# Schematic.net
KiCad netlist of a schematic drawn in Altium Designer
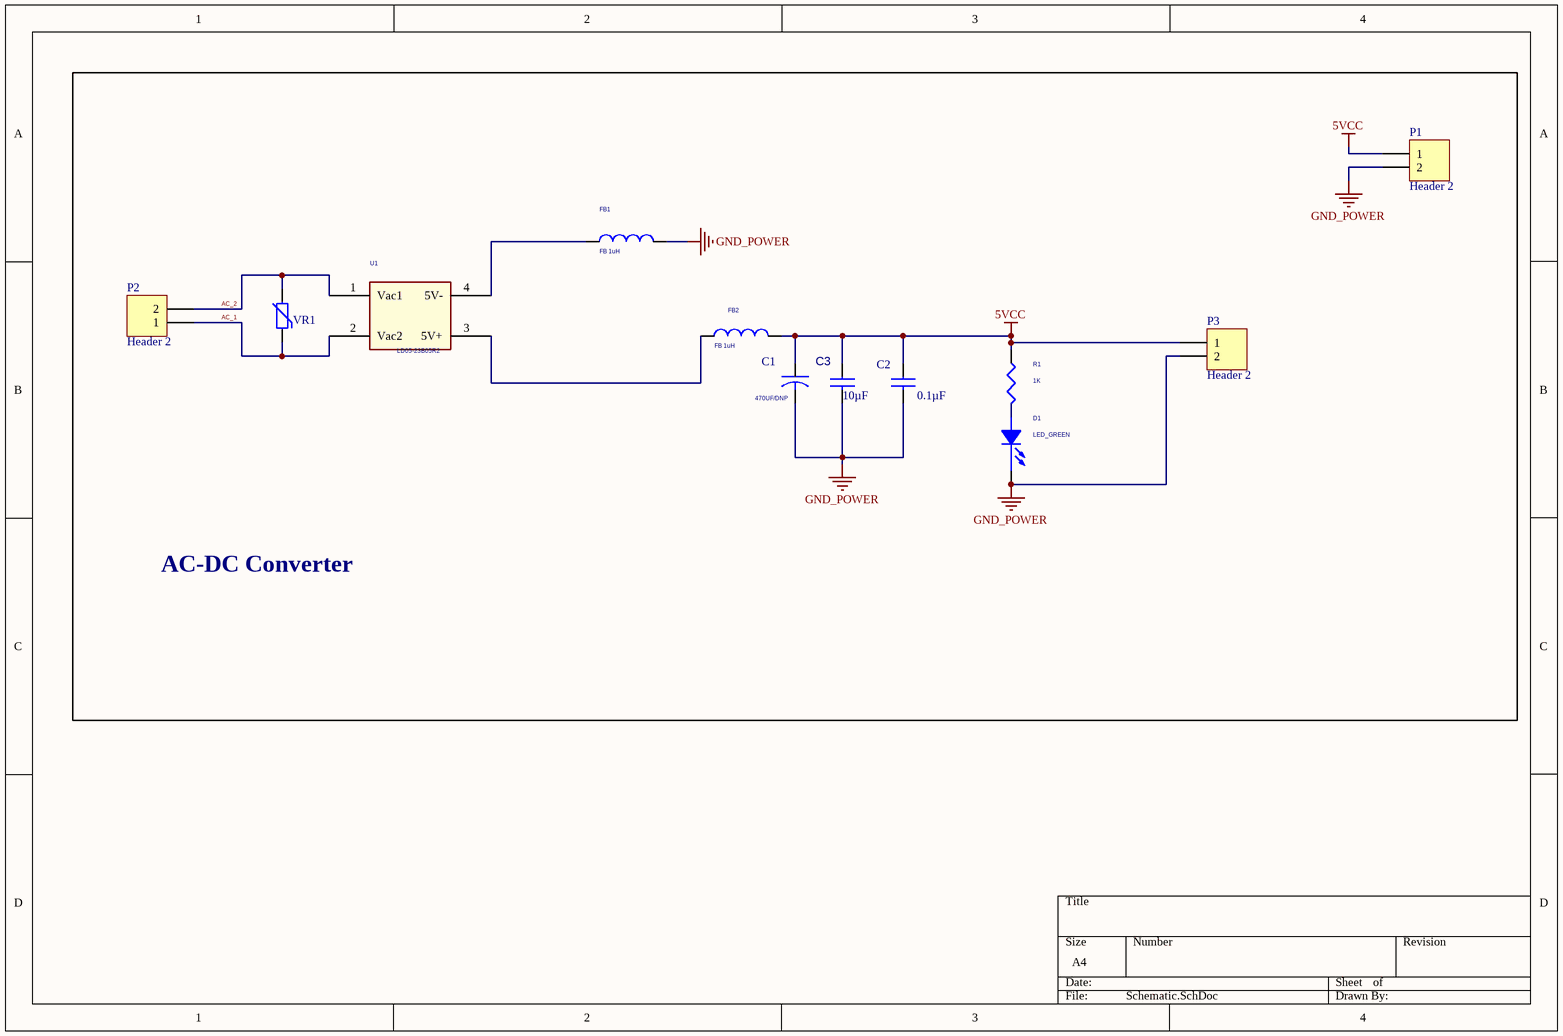
[diagram p0: Schematic.SchDoc]

(export (version "E")
  (design (tool "Eeschema 10.0.6"))
  (components
    (comp (ref "C1")
      (value "10µF")
      (footprint "0603 Capacitor")
      (description "CAP CER SMD 10µF/35V")
      (fields
        (field (name "MANUFACTURER") "Taiyo Yuden")
        (field (name "MANUFACTURER PART NUMBER") "GMK316AB7106KL-TR")
      )
      (libsource (lib "Passive Component") (part "CAP_C_10µF/35V"))
    )
    (comp (ref "C2")
      (value "0.1µF")
      (footprint "0603 Capacitor")
      (description "CAP CER SMD 0.1µF/50V")
      (fields
        (field (name "MANUFACTURER") "Yageo")
        (field (name "MANUFACTURER PART NUMBER") "CC0805ZRY5V9BB104")
      )
      (libsource (lib "Passive Component") (part "CAP_C_0.1µF/50V"))
    )
    (comp (ref "C3")
      (value "470UF/DNP")
      (footprint "Sensor Card:25ZLH470MEFC10X12.5")
      (description "CAP ALUM 470UF 20% 50V RADIAL")
      (fields (field (name "PART NUMBER") "P12400-ND"))
      (libsource (lib "*") (part "CAP"))
    )
    (comp (ref "D1")
      (value "LED_GREEN")
      (footprint "R_0603_W")
      (description "LED GREEN CLEAR THIN 0603 SMD")
      (fields
        (field (name "DISTRIBUTOR PART NUMBER") "160-1443-1-ND")
        (field (name "MANUFACTURER PART NUMBER") "160-1443-2-ND")
      )
      (libsource (lib "*") (part "LED"))
    )
    (comp (ref "FB1")
      (value "FB 1uH")
      (footprint "0603 Capacitor")
      (description "FILTER CHIP 120 OHM 3A 0603")
      (fields
        (field (name "PART NUMBER") "MMZ2012Y152B")
        (field (name "DISTRIBUTOR PART NUMBER") "1276-6357-1-ND")
      )
      (libsource (lib "*") (part "INDUCTOR"))
    )
    (comp (ref "FB2")
      (value "FB 1uH")
      (footprint "0603 Capacitor")
      (description "FILTER CHIP 120 OHM 3A 0603")
      (fields
        (field (name "DISTRIBUTOR PART NUMBER") "1276-6357-1-ND")
        (field (name "MANUFACTURER PART NUMBER") "490-4004-2-ND")
      )
      (libsource (lib "*") (part "INDUCTOR"))
    )
    (comp (ref "P1")
      (value "Header 2")
      (footprint "Miscellaneous Connectors:HDR1X2")
      (description "Header, 2-Pin")
      (fields (field (name "PUBLISHER") "Altium Limited"))
      (libsource (lib "Miscellaneous Connectors") (part "Header 2"))
    )
    (comp (ref "P2")
      (value "Header 2")
      (footprint "TE 282834-2")
      (description "Header, 2-Pin")
      (fields (field (name "PUBLISHER") "Altium Limited"))
      (libsource (lib "") (part "Header 2_1"))
    )
    (comp (ref "P3")
      (value "Header 2")
      (footprint "Miscellaneous Connectors:HDR1X2")
      (description "Header, 2-Pin")
      (fields (field (name "PUBLISHER") "Altium Limited"))
      (libsource (lib "Miscellaneous Connectors") (part "Header 2"))
    )
    (comp (ref "R1")
      (value "1K")
      (footprint "R_0603_W")
      (description "RES SMD 1K OHM 5% 1/10W 0603")
      (fields (field (name "PART NUMBER") "311-1.0KGRTR-ND"))
      (libsource (lib "*") (part "R"))
    )
    (comp (ref "U1")
      (value "LD05-23B05R2")
      (footprint "CONV_LD05-23B03R2")
      (fields (field (name "PART NUMBER") "MOV-10D431KTRCT-ND"))
      (libsource (lib "*") (part "2_PIN_PSH_BTTN_6"))
    )
    (comp (ref "VR1")
      (value "~")
      (footprint "Mov")
      (description "SMT Resistor")
      (libsource (lib "Passive Component") (part "Metal Oxide Variaster"))
    )
  )
  (nets
    (net (code "1") (name "/AC_1") (class "Default")
      (node (ref "P2") (pin "1") (pinfunction "1_1") (pintype "passive"))
      (node (ref "U1") (pin "2") (pinfunction "Vac2_2") (pintype "passive"))
      (node (ref "VR1") (pin "1") (pinfunction "1_1") (pintype "passive"))
    )
    (net (code "2") (name "/AC_2") (class "Default")
      (node (ref "P2") (pin "2") (pinfunction "2_2") (pintype "passive"))
      (node (ref "U1") (pin "1") (pinfunction "Vac1_1") (pintype "passive"))
      (node (ref "VR1") (pin "2") (pinfunction "2_2") (pintype "passive"))
    )
    (net (code "3") (name "5VCC") (class "Default")
      (node (ref "C1") (pin "1") (pinfunction "1_1") (pintype "passive"))
      (node (ref "C2") (pin "1") (pinfunction "1_1") (pintype "passive"))
      (node (ref "C3") (pin "1") (pinfunction "1_1") (pintype "passive"))
      (node (ref "FB2") (pin "2") (pinfunction "2_2") (pintype "passive"))
      (node (ref "P1") (pin "1") (pinfunction "1_1") (pintype "passive"))
      (node (ref "P3") (pin "1") (pinfunction "1_1") (pintype "passive"))
      (node (ref "R1") (pin "1") (pinfunction "1_1") (pintype "passive"))
    )
    (net (code "4") (name "GND_POWER") (class "Default")
      (node (ref "C1") (pin "2") (pinfunction "2_2") (pintype "passive"))
      (node (ref "C2") (pin "2") (pinfunction "2_2") (pintype "passive"))
      (node (ref "C3") (pin "2") (pinfunction "2_2") (pintype "passive"))
      (node (ref "D1") (pin "2") (pinfunction "CATHODE_2") (pintype "passive"))
      (node (ref "FB1") (pin "2") (pinfunction "2_2") (pintype "passive"))
      (node (ref "P1") (pin "2") (pinfunction "2_2") (pintype "passive"))
      (node (ref "P3") (pin "2") (pinfunction "2_2") (pintype "passive"))
    )
    (net (code "5") (name "Net-(D1-ANODE)") (class "Default")
      (node (ref "D1") (pin "1") (pinfunction "ANODE_1") (pintype "passive"))
      (node (ref "R1") (pin "2") (pinfunction "2_2") (pintype "passive"))
    )
    (net (code "6") (name "Net-(U1-5V+)") (class "Default")
      (node (ref "FB2") (pin "1") (pinfunction "1_1") (pintype "passive"))
      (node (ref "U1") (pin "3") (pinfunction "5V+_3") (pintype "passive"))
    )
    (net (code "7") (name "Net-(U1-5V-)") (class "Default")
      (node (ref "FB1") (pin "1") (pinfunction "1_1") (pintype "passive"))
      (node (ref "U1") (pin "4") (pinfunction "5V-_4") (pintype "passive"))
    )
  )
)
